# interface.net
KiCad netlist of a schematic drawn in Altium Designer
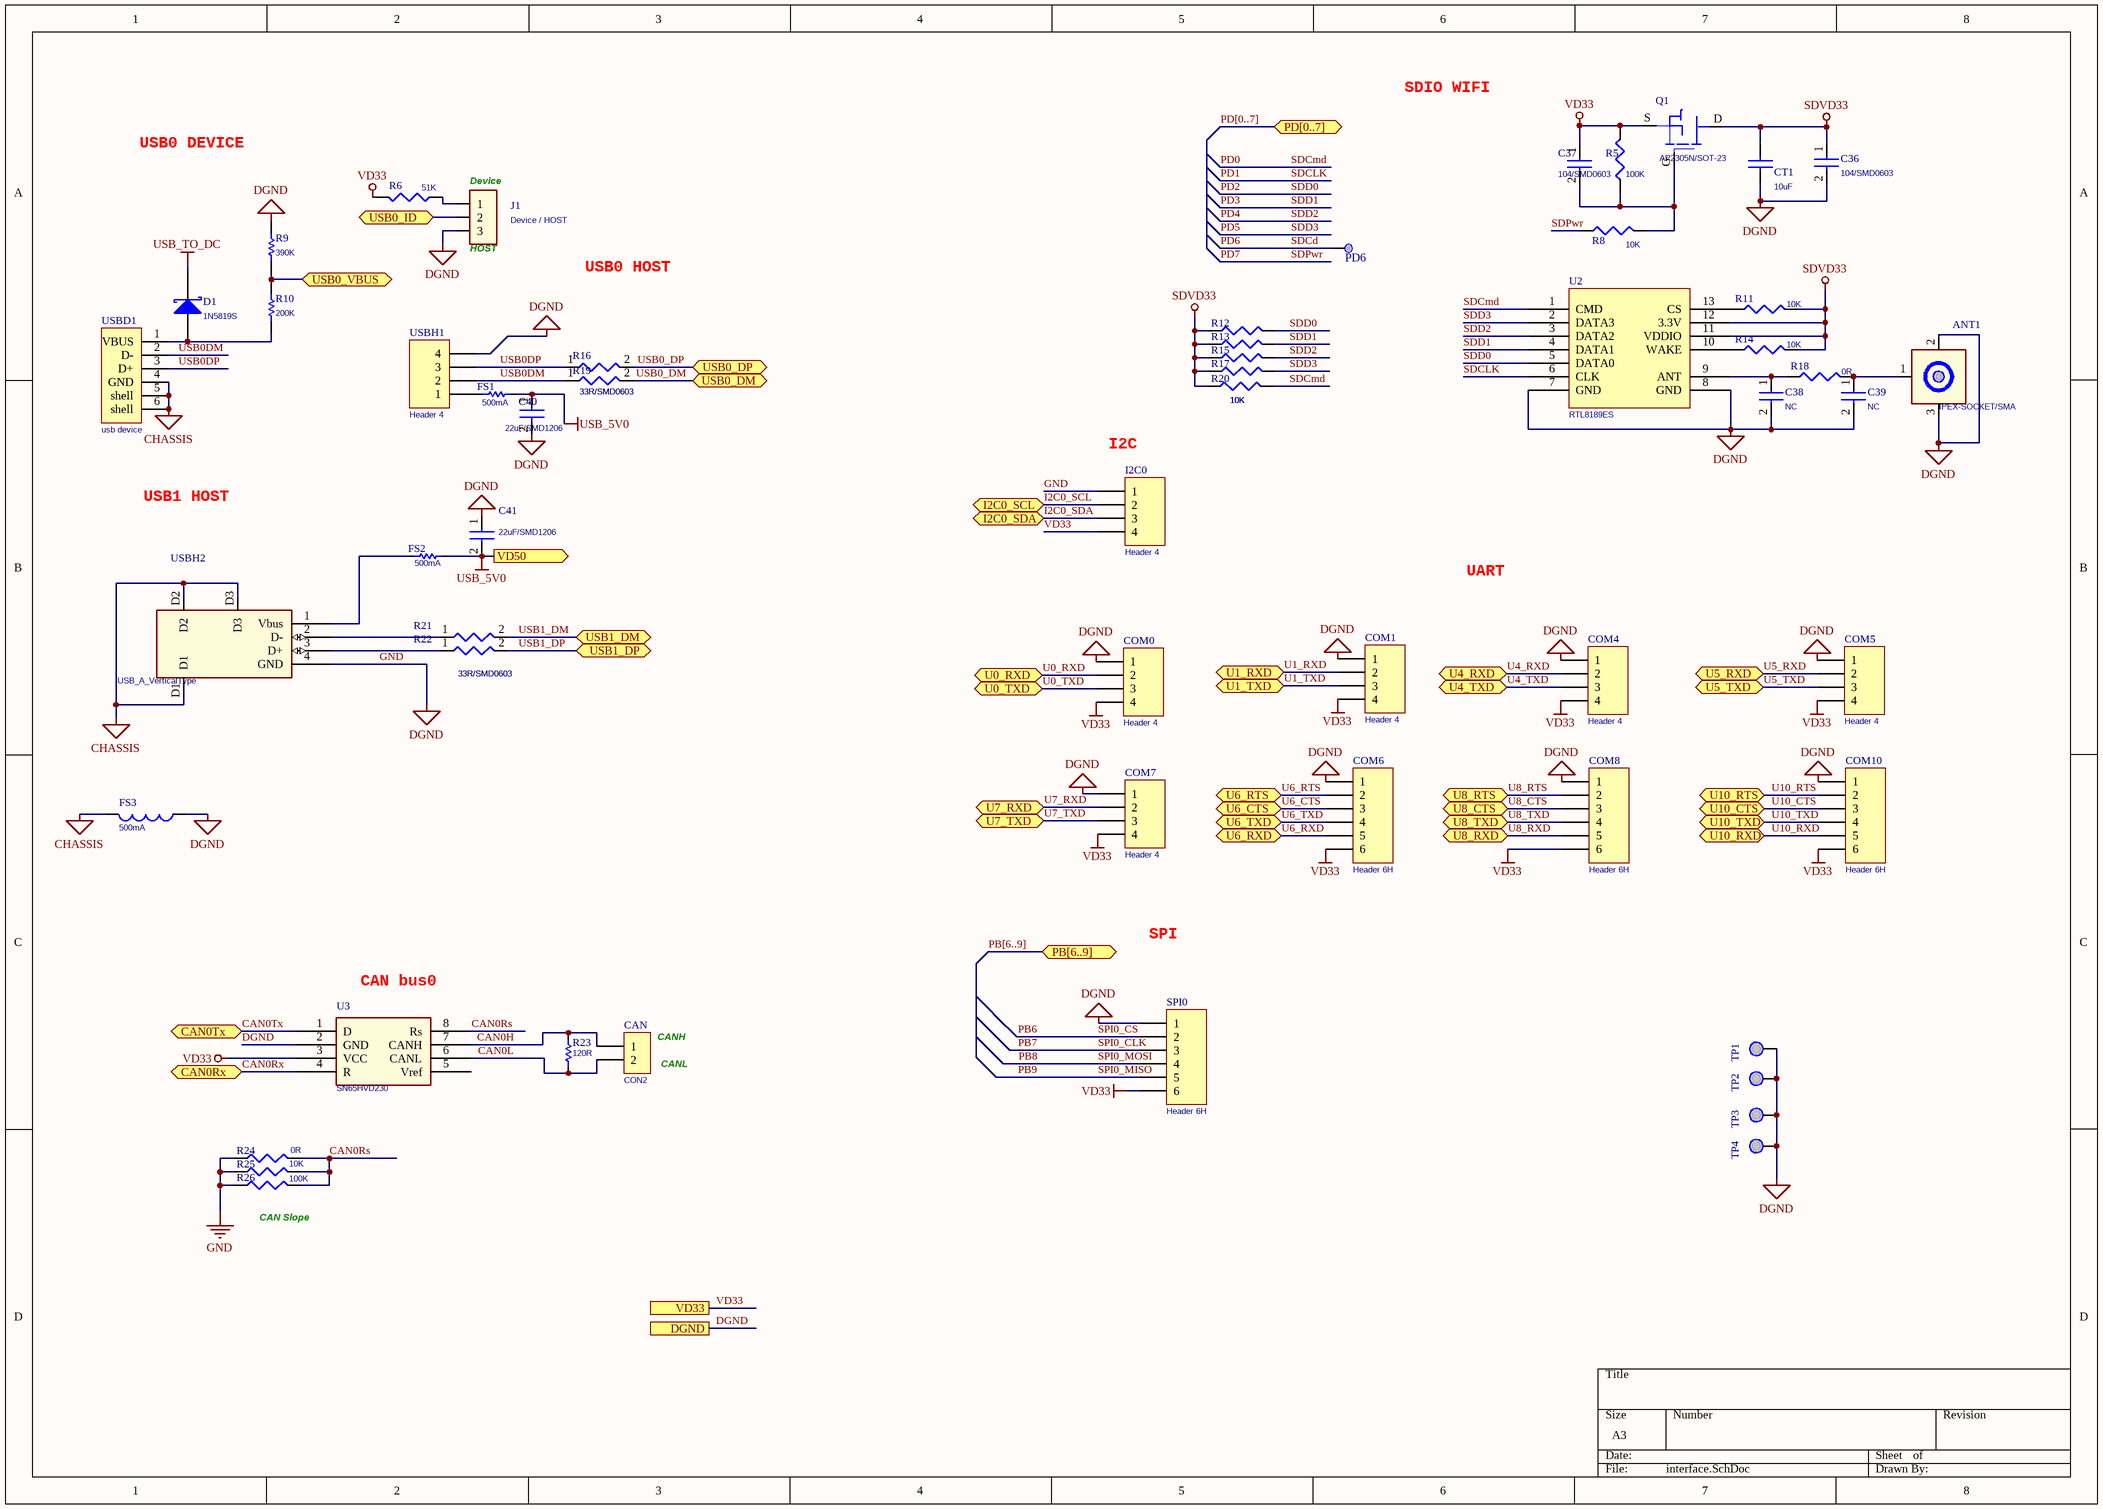
[diagram p0: interface.SchDoc]

(export (version "E")
  (design (tool "Eeschema 10.0.6"))
  (components
    (comp (ref "ANT1")
      (value "IPEX-SOCKET/SMA")
      (footprint "ANT_PIX")
      (libsource (lib "*") (part "IPEX-SOCKET/SMA"))
    )
    (comp (ref "C36") (value "104/SMD0603") (footprint "0603C") (libsource (lib "*") (part "C/SMD0603")))
    (comp (ref "C37") (value "104/SMD0603") (footprint "0603C") (libsource (lib "*") (part "C/SMD0603")))
    (comp (ref "C38") (value "NC") (footprint "0603C") (libsource (lib "*") (part "C/SMD0603")))
    (comp (ref "C39") (value "NC") (footprint "0603C") (libsource (lib "*") (part "C/SMD0603")))
    (comp (ref "C40") (value "22uF/SMD1206") (footprint "C0805") (libsource (lib "*") (part "C/SMD1206")))
    (comp (ref "C41") (value "22uF/SMD1206") (footprint "C0805") (libsource (lib "*") (part "C/SMD1206")))
    (comp (ref "CAN")
      (value "CON2")
      (footprint "INTERFACE-2")
      (description "Connector")
      (libsource (lib "changyong") (part "CON2"))
    )
    (comp (ref "COM0")
      (value "Header 4")
      (footprint "PH04S_180")
      (description "Header, 4-Pin")
      (fields (field (name "PUBLISHER") "Altium Limited"))
      (libsource (lib "Miscellaneous Connectors") (part "Header 4"))
    )
    (comp (ref "COM1")
      (value "Header 4")
      (footprint "PH04S_180")
      (description "Header, 4-Pin")
      (fields (field (name "PUBLISHER") "Altium Limited"))
      (libsource (lib "Miscellaneous Connectors") (part "Header 4"))
    )
    (comp (ref "COM4")
      (value "Header 4")
      (footprint "PH04S_180")
      (description "Header, 4-Pin")
      (fields (field (name "PUBLISHER") "Altium Limited"))
      (libsource (lib "Miscellaneous Connectors") (part "Header 4"))
    )
    (comp (ref "COM5")
      (value "Header 4")
      (footprint "PH04S_180")
      (description "Header, 4-Pin")
      (fields (field (name "PUBLISHER") "Altium Limited"))
      (libsource (lib "Miscellaneous Connectors") (part "Header 4"))
    )
    (comp (ref "COM6")
      (value "Header 6H")
      (footprint "PH06S")
      (description "Header, 6-Pin, Right Angle")
      (fields (field (name "PUBLISHER") "Altium Limited"))
      (libsource (lib "Miscellaneous Connectors") (part "Header 6H"))
    )
    (comp (ref "COM7")
      (value "Header 4")
      (footprint "PH04S_180")
      (description "Header, 4-Pin")
      (fields (field (name "PUBLISHER") "Altium Limited"))
      (libsource (lib "Miscellaneous Connectors") (part "Header 4"))
    )
    (comp (ref "COM8")
      (value "Header 6H")
      (footprint "PH06S")
      (description "Header, 6-Pin, Right Angle")
      (fields (field (name "PUBLISHER") "Altium Limited"))
      (libsource (lib "Miscellaneous Connectors") (part "Header 6H"))
    )
    (comp (ref "COM10")
      (value "Header 6H")
      (footprint "PH06S")
      (description "Header, 6-Pin, Right Angle")
      (fields (field (name "PUBLISHER") "Altium Limited"))
      (libsource (lib "Miscellaneous Connectors") (part "Header 6H"))
    )
    (comp (ref "CT1") (value "10uF") (footprint "C0805") (libsource (lib "*") (part "CAP NP_Dup1")))
    (comp (ref "D1")
      (value "1N5819S")
      (footprint "SOD-123_1N5819HW")
      (description "Schottky Rectifier")
      (fields (field (name "PUBLISHER") "Altium Limited"))
      (libsource (lib "Miscellaneous Devices") (part "Diode 10TQ035"))
    )
    (comp (ref "FS1")
      (value "500mA")
      (footprint "0805")
      (description "Resistor")
      (fields (field (name "PUBLISHER") "*"))
      (libsource (lib "*") (part "Res1"))
    )
    (comp (ref "FS2")
      (value "500mA")
      (footprint "0805")
      (description "Resistor")
      (fields (field (name "PUBLISHER") "*"))
      (libsource (lib "*") (part "Res1"))
    )
    (comp (ref "FS3")
      (value "500mA")
      (footprint "0805R")
      (description "Inductor")
      (fields (field (name "PUBLISHER") "Altium Limited"))
      (libsource (lib "MYSTM32") (part "Inductor"))
    )
    (comp (ref "I2C0")
      (value "Header 4")
      (footprint "PH04S_180")
      (description "Header, 4-Pin")
      (fields (field (name "PUBLISHER") "Altium Limited"))
      (libsource (lib "Miscellaneous Connectors") (part "Header 4"))
    )
    (comp (ref "J1") (value "Device / HOST") (footprint "SIP3") (libsource (lib "*") (part "CON3")))
    (comp (ref "PD6") (value "TP") (footprint "TP") (libsource (lib "changyong") (part "TP")))
    (comp (ref "Q1")
      (value "AP2305N/SOT-23")
      (footprint "AP2305N_SOT23")
      (libsource (lib "changyong") (part "AP2305N/SOT-23"))
    )
    (comp (ref "R5") (value "100K") (footprint "0603R") (libsource (lib "*") (part "R_Dup1")))
    (comp (ref "R6") (value "51K") (footprint "0603R") (libsource (lib "*") (part "R_Dup1")))
    (comp (ref "R8") (value "10K") (footprint "0603R") (libsource (lib "*") (part "R_Dup1")))
    (comp (ref "R9")
      (value "390K")
      (footprint "0603R")
      (description "Resistor")
      (fields (field (name "PUBLISHER") "Altium Limited"))
      (libsource (lib "STM32F107VCT") (part "res1"))
    )
    (comp (ref "R10")
      (value "200K")
      (footprint "0603R")
      (description "Resistor")
      (fields (field (name "PUBLISHER") "Altium Limited"))
      (libsource (lib "STM32F107VCT") (part "res1"))
    )
    (comp (ref "R11") (value "10K") (footprint "0603R") (libsource (lib "*") (part "R_Dup1")))
    (comp (ref "R12") (value "10K") (footprint "0603R") (libsource (lib "*") (part "R_Dup1")))
    (comp (ref "R13") (value "10K") (footprint "0603R") (libsource (lib "*") (part "R_Dup1")))
    (comp (ref "R14") (value "10K") (footprint "0603R") (libsource (lib "*") (part "R_Dup1")))
    (comp (ref "R15") (value "10K") (footprint "0603R") (libsource (lib "*") (part "R_Dup1")))
    (comp (ref "R16") (value "33R/SMD0603") (footprint "0603R") (libsource (lib "*") (part "R/SMD0603_Dup1")))
    (comp (ref "R17") (value "10K") (footprint "0603R") (libsource (lib "*") (part "R_Dup1")))
    (comp (ref "R18") (value "0R") (footprint "0603R") (libsource (lib "*") (part "R_Dup1")))
    (comp (ref "R19") (value "33R/SMD0603") (footprint "0603R") (libsource (lib "*") (part "R/SMD0603_Dup1")))
    (comp (ref "R20") (value "10K") (footprint "0603R") (libsource (lib "*") (part "R_Dup1")))
    (comp (ref "R21") (value "33R/SMD0603") (footprint "0603R") (libsource (lib "*") (part "R/SMD0603_Dup1")))
    (comp (ref "R22") (value "33R/SMD0603") (footprint "0603R") (libsource (lib "*") (part "R/SMD0603_Dup1")))
    (comp (ref "R23")
      (value "120R")
      (footprint "0805")
      (description "Resistor")
      (fields (field (name "PUBLISHER") "*"))
      (libsource (lib "*") (part "Res1"))
    )
    (comp (ref "R24") (value "0R") (footprint "0603R") (libsource (lib "*") (part "R_Dup1")))
    (comp (ref "R25") (value "10K") (footprint "0603R") (libsource (lib "*") (part "R_Dup1")))
    (comp (ref "R26") (value "100K") (footprint "0603R") (libsource (lib "*") (part "R_Dup1")))
    (comp (ref "SPI0")
      (value "Header 6H")
      (footprint "PH06S")
      (description "Header, 6-Pin, Right Angle")
      (fields (field (name "PUBLISHER") "Altium Limited"))
      (libsource (lib "Miscellaneous Connectors") (part "Header 6H"))
    )
    (comp (ref "TP1")
      (value "TEST POINT")
      (footprint "HOLE53")
      (libsource (lib "*") (part "TEST POINT_Dup1"))
    )
    (comp (ref "TP2")
      (value "TEST POINT")
      (footprint "HOLE53")
      (libsource (lib "*") (part "TEST POINT_Dup1"))
    )
    (comp (ref "TP3")
      (value "TEST POINT")
      (footprint "HOLE53")
      (libsource (lib "*") (part "TEST POINT_Dup1"))
    )
    (comp (ref "TP4")
      (value "TEST POINT")
      (footprint "HOLE53")
      (libsource (lib "*") (part "TEST POINT_Dup1"))
    )
    (comp (ref "U2")
      (value "RTL8189ES")
      (footprint "RTL8189ES")
      (libsource (lib "changyong") (part "RTL8189ES"))
    )
    (comp (ref "U3")
      (value "SN65HVD230")
      (footprint "SOIC127P800-8N")
      (libsource (lib "*") (part "SN65HVD230"))
    )
    (comp (ref "USBD1")
      (value "usb device")
      (footprint "USB-MICRO-AB")
      (description "USB接口")
      (libsource (lib "MYSTM32") (part "USB"))
    )
    (comp (ref "USBH1")
      (value "Header 4")
      (footprint "PH04S_180")
      (description "Header, 4-Pin")
      (fields (field (name "PUBLISHER") "Altium Limited"))
      (libsource (lib "") (part "Header 4_1"))
    )
    (comp (ref "USBH2")
      (value "USB_A_VerticalType")
      (footprint "USB/A 90")
      (libsource (lib "*") (part "USB_A_VerticalType"))
    )
  )
  (nets
    (net (code "1") (name "/CAN0H") (class "Default")
      (node (ref "CAN") (pin "2") (pinfunction "1_2") (pintype "passive"))
      (node (ref "R23") (pin "2") (pinfunction "2_2") (pintype "passive"))
      (node (ref "U3") (pin "7") (pinfunction "CANH_7") (pintype "passive"))
    )
    (net (code "2") (name "/CAN0L") (class "Default")
      (node (ref "CAN") (pin "1") (pinfunction "2_1") (pintype "passive"))
      (node (ref "R23") (pin "1") (pinfunction "1_1") (pintype "passive"))
      (node (ref "U3") (pin "6") (pinfunction "CANL_6") (pintype "passive"))
    )
    (net (code "3") (name "/CAN0Rs") (class "Default")
      (node (ref "R24") (pin "2") (pinfunction "2_2") (pintype "passive"))
      (node (ref "R25") (pin "2") (pinfunction "2_2") (pintype "passive"))
      (node (ref "R26") (pin "2") (pinfunction "2_2") (pintype "passive"))
      (node (ref "U3") (pin "8") (pinfunction "Rs_8") (pintype "passive"))
    )
    (net (code "4") (name "/CAN0Rx") (class "Default")
      (node (ref "U3") (pin "4") (pinfunction "R_4") (pintype "passive"))
    )
    (net (code "5") (name "/CAN0Tx") (class "Default")
      (node (ref "U3") (pin "1") (pinfunction "D_1") (pintype "passive"))
    )
    (net (code "6") (name "/I2C0_SCL") (class "Default")
      (node (ref "I2C0") (pin "2") (pinfunction "2_2") (pintype "passive"))
    )
    (net (code "7") (name "/I2C0_SDA") (class "Default")
      (node (ref "I2C0") (pin "3") (pinfunction "3_3") (pintype "passive"))
    )
    (net (code "8") (name "/PB6") (class "Default")
      (node (ref "SPI0") (pin "2") (pinfunction "2_2") (pintype "passive"))
    )
    (net (code "9") (name "/PB7") (class "Default")
      (node (ref "SPI0") (pin "3") (pinfunction "3_3") (pintype "passive"))
    )
    (net (code "10") (name "/PB8") (class "Default")
      (node (ref "SPI0") (pin "4") (pinfunction "4_4") (pintype "passive"))
    )
    (net (code "11") (name "/PB9") (class "Default")
      (node (ref "SPI0") (pin "5") (pinfunction "5_5") (pintype "passive"))
    )
    (net (code "13") (name "/PD0") (class "Default")
      (node (ref "R20") (pin "1") (pinfunction "1_1") (pintype "passive"))
      (node (ref "U2") (pin "1") (pinfunction "CMD_1") (pintype "passive"))
    )
    (net (code "14") (name "/PD1") (class "Default")
      (node (ref "U2") (pin "6") (pinfunction "CLK_6") (pintype "passive"))
    )
    (net (code "15") (name "/PD2") (class "Default")
      (node (ref "R12") (pin "1") (pinfunction "1_1") (pintype "passive"))
      (node (ref "U2") (pin "5") (pinfunction "DATA0_5") (pintype "passive"))
    )
    (net (code "16") (name "/PD3") (class "Default")
      (node (ref "R13") (pin "1") (pinfunction "1_1") (pintype "passive"))
      (node (ref "U2") (pin "4") (pinfunction "DATA1_4") (pintype "passive"))
    )
    (net (code "17") (name "/PD4") (class "Default")
      (node (ref "R15") (pin "1") (pinfunction "1_1") (pintype "passive"))
      (node (ref "U2") (pin "3") (pinfunction "DATA2_3") (pintype "passive"))
    )
    (net (code "18") (name "/PD5") (class "Default")
      (node (ref "R17") (pin "1") (pinfunction "1_1") (pintype "passive"))
      (node (ref "U2") (pin "2") (pinfunction "DATA3_2") (pintype "passive"))
    )
    (net (code "19") (name "/PD6") (class "Default")
      (node (ref "PD6") (pin "1") (pinfunction "1_1") (pintype "passive"))
    )
    (net (code "20") (name "/PD7") (class "Default")
      (node (ref "R8") (pin "2") (pinfunction "2_2") (pintype "passive"))
    )
    (net (code "22") (name "/U0_RXD") (class "Default")
      (node (ref "COM0") (pin "2") (pinfunction "2_2") (pintype "passive"))
    )
    (net (code "23") (name "/U0_TXD") (class "Default")
      (node (ref "COM0") (pin "3") (pinfunction "3_3") (pintype "passive"))
    )
    (net (code "24") (name "/U1_RXD") (class "Default")
      (node (ref "COM1") (pin "2") (pinfunction "2_2") (pintype "passive"))
    )
    (net (code "25") (name "/U1_TXD") (class "Default")
      (node (ref "COM1") (pin "3") (pinfunction "3_3") (pintype "passive"))
    )
    (net (code "26") (name "/U4_RXD") (class "Default")
      (node (ref "COM4") (pin "2") (pinfunction "2_2") (pintype "passive"))
    )
    (net (code "27") (name "/U4_TXD") (class "Default")
      (node (ref "COM4") (pin "3") (pinfunction "3_3") (pintype "passive"))
    )
    (net (code "28") (name "/U5_RXD") (class "Default")
      (node (ref "COM5") (pin "2") (pinfunction "2_2") (pintype "passive"))
    )
    (net (code "29") (name "/U5_TXD") (class "Default")
      (node (ref "COM5") (pin "3") (pinfunction "3_3") (pintype "passive"))
    )
    (net (code "30") (name "/U6_CTS") (class "Default")
      (node (ref "COM6") (pin "3") (pinfunction "3_3") (pintype "passive"))
    )
    (net (code "31") (name "/U6_RTS") (class "Default")
      (node (ref "COM6") (pin "2") (pinfunction "2_2") (pintype "passive"))
    )
    (net (code "32") (name "/U6_RXD") (class "Default")
      (node (ref "COM6") (pin "5") (pinfunction "5_5") (pintype "passive"))
    )
    (net (code "33") (name "/U6_TXD") (class "Default")
      (node (ref "COM6") (pin "4") (pinfunction "4_4") (pintype "passive"))
    )
    (net (code "34") (name "/U7_RXD") (class "Default")
      (node (ref "COM7") (pin "2") (pinfunction "2_2") (pintype "passive"))
    )
    (net (code "35") (name "/U7_TXD") (class "Default")
      (node (ref "COM7") (pin "3") (pinfunction "3_3") (pintype "passive"))
    )
    (net (code "36") (name "/U8_CTS") (class "Default")
      (node (ref "COM8") (pin "3") (pinfunction "3_3") (pintype "passive"))
    )
    (net (code "37") (name "/U8_RTS") (class "Default")
      (node (ref "COM8") (pin "2") (pinfunction "2_2") (pintype "passive"))
    )
    (net (code "38") (name "/U8_RXD") (class "Default")
      (node (ref "COM8") (pin "5") (pinfunction "5_5") (pintype "passive"))
    )
    (net (code "39") (name "/U8_TXD") (class "Default")
      (node (ref "COM8") (pin "4") (pinfunction "4_4") (pintype "passive"))
    )
    (net (code "40") (name "/U10_CTS") (class "Default")
      (node (ref "COM10") (pin "3") (pinfunction "3_3") (pintype "passive"))
    )
    (net (code "41") (name "/U10_RTS") (class "Default")
      (node (ref "COM10") (pin "2") (pinfunction "2_2") (pintype "passive"))
    )
    (net (code "42") (name "/U10_RXD") (class "Default")
      (node (ref "COM10") (pin "5") (pinfunction "5_5") (pintype "passive"))
    )
    (net (code "43") (name "/U10_TXD") (class "Default")
      (node (ref "COM10") (pin "4") (pinfunction "4_4") (pintype "passive"))
    )
    (net (code "44") (name "/USB0DM") (class "Default")
      (node (ref "R19") (pin "1") (pinfunction "1_1") (pintype "passive"))
      (node (ref "USBD1") (pin "2") (pinfunction "D-_2") (pintype "passive"))
      (node (ref "USBH1") (pin "2") (pinfunction "2_2") (pintype "passive"))
    )
    (net (code "45") (name "/USB0DP") (class "Default")
      (node (ref "R16") (pin "1") (pinfunction "1_1") (pintype "passive"))
      (node (ref "USBD1") (pin "3") (pinfunction "D+_3") (pintype "passive"))
      (node (ref "USBH1") (pin "3") (pinfunction "3_3") (pintype "passive"))
    )
    (net (code "46") (name "/USB0_DM") (class "Default")
      (node (ref "R19") (pin "2") (pinfunction "2_2") (pintype "passive"))
    )
    (net (code "47") (name "/USB0_DP") (class "Default")
      (node (ref "R16") (pin "2") (pinfunction "2_2") (pintype "passive"))
    )
    (net (code "48") (name "/USB0_ID") (class "Default")
      (node (ref "J1") (pin "2") (pinfunction "2_2") (pintype "passive"))
    )
    (net (code "49") (name "/USB0_VBUS") (class "Default")
      (node (ref "R10") (pin "2") (pinfunction "2_2") (pintype "passive"))
      (node (ref "R9") (pin "2") (pinfunction "2_2") (pintype "passive"))
    )
    (net (code "50") (name "/USB1_DM") (class "Default")
      (node (ref "R21") (pin "2") (pinfunction "2_2") (pintype "passive"))
    )
    (net (code "51") (name "/USB1_DP") (class "Default")
      (node (ref "R22") (pin "2") (pinfunction "2_2") (pintype "passive"))
    )
    (net (code "52") (name "CHASSIS") (class "Default")
      (node (ref "FS3") (pin "2") (pinfunction "2_2") (pintype "passive"))
      (node (ref "USBD1") (pin "4") (pinfunction "GND_4") (pintype "passive"))
      (node (ref "USBD1") (pin "5") (pinfunction "shell_5") (pintype "passive"))
      (node (ref "USBD1") (pin "6") (pinfunction "shell_6") (pintype "passive"))
      (node (ref "USBH2") (pin "D1") (pinfunction "D1_D1") (pintype "passive"))
      (node (ref "USBH2") (pin "D2") (pinfunction "D2_D2") (pintype "passive"))
      (node (ref "USBH2") (pin "D3") (pinfunction "D3_D3") (pintype "passive"))
    )
    (net (code "53") (name "DGND") (class "Default")
      (node (ref "ANT1") (pin "2") (pinfunction "2_2") (pintype "passive"))
      (node (ref "ANT1") (pin "3") (pinfunction "3_3") (pintype "passive"))
      (node (ref "C36") (pin "2") (pinfunction "2_2") (pintype "passive"))
      (node (ref "C38") (pin "2") (pinfunction "2_2") (pintype "passive"))
      (node (ref "C39") (pin "2") (pinfunction "2_2") (pintype "passive"))
      (node (ref "C40") (pin "2") (pinfunction "2_2") (pintype "passive"))
      (node (ref "C41") (pin "1") (pinfunction "1_1") (pintype "passive"))
      (node (ref "COM0") (pin "1") (pinfunction "1_1") (pintype "passive"))
      (node (ref "COM1") (pin "1") (pinfunction "1_1") (pintype "passive"))
      (node (ref "COM10") (pin "1") (pinfunction "1_1") (pintype "passive"))
      (node (ref "COM4") (pin "1") (pinfunction "1_1") (pintype "passive"))
      (node (ref "COM5") (pin "1") (pinfunction "1_1") (pintype "passive"))
      (node (ref "COM6") (pin "1") (pinfunction "1_1") (pintype "passive"))
      (node (ref "COM7") (pin "1") (pinfunction "1_1") (pintype "passive"))
      (node (ref "COM8") (pin "1") (pinfunction "1_1") (pintype "passive"))
      (node (ref "CT1") (pin "1") (pinfunction "1_1") (pintype "passive"))
      (node (ref "FS3") (pin "1") (pinfunction "1_1") (pintype "passive"))
      (node (ref "I2C0") (pin "1") (pinfunction "1_1") (pintype "passive"))
      (node (ref "J1") (pin "3") (pinfunction "3_3") (pintype "passive"))
      (node (ref "R24") (pin "1") (pinfunction "1_1") (pintype "passive"))
      (node (ref "R25") (pin "1") (pinfunction "1_1") (pintype "passive"))
      (node (ref "R26") (pin "1") (pinfunction "1_1") (pintype "passive"))
      (node (ref "R9") (pin "1") (pinfunction "1_1") (pintype "passive"))
      (node (ref "SPI0") (pin "1") (pinfunction "1_1") (pintype "passive"))
      (node (ref "TP1") (pin "1") (pinfunction "TP_1") (pintype "passive"))
      (node (ref "TP2") (pin "1") (pinfunction "TP_1") (pintype "passive"))
      (node (ref "TP3") (pin "1") (pinfunction "TP_1") (pintype "passive"))
      (node (ref "TP4") (pin "1") (pinfunction "TP_1") (pintype "passive"))
      (node (ref "U2") (pin "7") (pinfunction "GND_7") (pintype "passive"))
      (node (ref "U2") (pin "8") (pinfunction "GND_8") (pintype "passive"))
      (node (ref "U3") (pin "2") (pinfunction "GND_2") (pintype "passive"))
      (node (ref "USBH1") (pin "4") (pinfunction "4_4") (pintype "passive"))
      (node (ref "USBH2") (pin "4") (pinfunction "GND_4") (pintype "power_in"))
    )
    (net (code "54") (name "Net-(ANT1-Pad1)") (class "Default")
      (node (ref "ANT1") (pin "1") (pinfunction "1_1") (pintype "passive"))
      (node (ref "C39") (pin "1") (pinfunction "1_1") (pintype "passive"))
      (node (ref "R18") (pin "1") (pinfunction "1_1") (pintype "passive"))
    )
    (net (code "55") (name "Net-(D1-A)") (class "Default")
      (node (ref "D1") (pin "2") (pinfunction "A_2") (pintype "passive"))
      (node (ref "R10") (pin "1") (pinfunction "1_1") (pintype "passive"))
      (node (ref "USBD1") (pin "1") (pinfunction "VBUS_1") (pintype "passive"))
    )
    (net (code "56") (name "Net-(FS1-Pad2)") (class "Default")
      (node (ref "FS1") (pin "2") (pinfunction "2_2") (pintype "passive"))
      (node (ref "USBH1") (pin "1") (pinfunction "1_1") (pintype "passive"))
    )
    (net (code "57") (name "Net-(J1-Pad1)") (class "Default")
      (node (ref "J1") (pin "1") (pinfunction "1_1") (pintype "passive"))
      (node (ref "R6") (pin "1") (pinfunction "1_1") (pintype "passive"))
    )
    (net (code "58") (name "Net-(Q1-2)") (class "Default")
      (node (ref "C37") (pin "2") (pinfunction "2_2") (pintype "passive"))
      (node (ref "Q1") (pin "G") (pinfunction "2_G") (pintype "passive"))
      (node (ref "R5") (pin "1") (pinfunction "1_1") (pintype "passive"))
      (node (ref "R8") (pin "1") (pinfunction "1_1") (pintype "passive"))
    )
    (net (code "59") (name "Net-(U2-ANT)") (class "Default")
      (node (ref "C38") (pin "1") (pinfunction "1_1") (pintype "passive"))
      (node (ref "R18") (pin "2") (pinfunction "2_2") (pintype "passive"))
      (node (ref "U2") (pin "9") (pinfunction "ANT_9") (pintype "passive"))
    )
    (net (code "60") (name "Net-(U2-CS)") (class "Default")
      (node (ref "R11") (pin "2") (pinfunction "2_2") (pintype "passive"))
      (node (ref "U2") (pin "13") (pinfunction "CS_13") (pintype "passive"))
    )
    (net (code "61") (name "Net-(U2-WAKE)") (class "Default")
      (node (ref "R14") (pin "2") (pinfunction "2_2") (pintype "passive"))
      (node (ref "U2") (pin "10") (pinfunction "WAKE_10") (pintype "passive"))
    )
    (net (code "62") (name "Net-(USBH2-D+)") (class "Default")
      (node (ref "R22") (pin "1") (pinfunction "1_1") (pintype "passive"))
      (node (ref "USBH2") (pin "3") (pinfunction "D+_3") (pintype "bidirectional"))
    )
    (net (code "63") (name "Net-(USBH2-D-)") (class "Default")
      (node (ref "R21") (pin "1") (pinfunction "1_1") (pintype "passive"))
      (node (ref "USBH2") (pin "2") (pinfunction "D-_2") (pintype "bidirectional"))
    )
    (net (code "64") (name "Net-(USBH2-Vbus)") (class "Default")
      (node (ref "FS2") (pin "2") (pinfunction "2_2") (pintype "passive"))
      (node (ref "USBH2") (pin "1") (pinfunction "Vbus_1") (pintype "power_in"))
    )
    (net (code "65") (name "SDVD33") (class "Default")
      (node (ref "C36") (pin "1") (pinfunction "1_1") (pintype "passive"))
      (node (ref "CT1") (pin "2") (pinfunction "2_2") (pintype "passive"))
      (node (ref "Q1") (pin "D") (pinfunction "1_D") (pintype "passive"))
      (node (ref "R11") (pin "1") (pinfunction "1_1") (pintype "passive"))
      (node (ref "R12") (pin "2") (pinfunction "2_2") (pintype "passive"))
      (node (ref "R13") (pin "2") (pinfunction "2_2") (pintype "passive"))
      (node (ref "R14") (pin "1") (pinfunction "1_1") (pintype "passive"))
      (node (ref "R15") (pin "2") (pinfunction "2_2") (pintype "passive"))
      (node (ref "R17") (pin "2") (pinfunction "2_2") (pintype "passive"))
      (node (ref "R20") (pin "2") (pinfunction "2_2") (pintype "passive"))
      (node (ref "U2") (pin "11") (pinfunction "VDDIO_11") (pintype "passive"))
      (node (ref "U2") (pin "12") (pinfunction "3.3V_12") (pintype "passive"))
    )
    (net (code "66") (name "USB_5V0") (class "Default")
      (node (ref "C40") (pin "1") (pinfunction "1_1") (pintype "passive"))
      (node (ref "C41") (pin "2") (pinfunction "2_2") (pintype "passive"))
      (node (ref "FS1") (pin "1") (pinfunction "1_1") (pintype "passive"))
      (node (ref "FS2") (pin "1") (pinfunction "1_1") (pintype "passive"))
    )
    (net (code "67") (name "USB_TO_DC") (class "Default")
      (node (ref "D1") (pin "1") (pinfunction "K_1") (pintype "passive"))
    )
    (net (code "68") (name "VD33") (class "Default")
      (node (ref "C37") (pin "1") (pinfunction "1_1") (pintype "passive"))
      (node (ref "COM0") (pin "4") (pinfunction "4_4") (pintype "passive"))
      (node (ref "COM1") (pin "4") (pinfunction "4_4") (pintype "passive"))
      (node (ref "COM10") (pin "6") (pinfunction "6_6") (pintype "passive"))
      (node (ref "COM4") (pin "4") (pinfunction "4_4") (pintype "passive"))
      (node (ref "COM5") (pin "4") (pinfunction "4_4") (pintype "passive"))
      (node (ref "COM6") (pin "6") (pinfunction "6_6") (pintype "passive"))
      (node (ref "COM7") (pin "4") (pinfunction "4_4") (pintype "passive"))
      (node (ref "COM8") (pin "6") (pinfunction "6_6") (pintype "passive"))
      (node (ref "I2C0") (pin "4") (pinfunction "4_4") (pintype "passive"))
      (node (ref "Q1") (pin "S") (pinfunction "3_S") (pintype "passive"))
      (node (ref "R5") (pin "2") (pinfunction "2_2") (pintype "passive"))
      (node (ref "R6") (pin "2") (pinfunction "2_2") (pintype "passive"))
      (node (ref "SPI0") (pin "6") (pinfunction "6_6") (pintype "passive"))
      (node (ref "U3") (pin "3") (pinfunction "VCC_3") (pintype "passive"))
    )
    (net (code "69") (name "unconnected-(U3-Vref-Pad5)") (class "Default")
      (node (ref "U3") (pin "5") (pinfunction "Vref_5") (pintype "passive"))
    )
  )
)
